# grip_strength_schematic.net
KiCad netlist of a schematic drawn in EAGLE
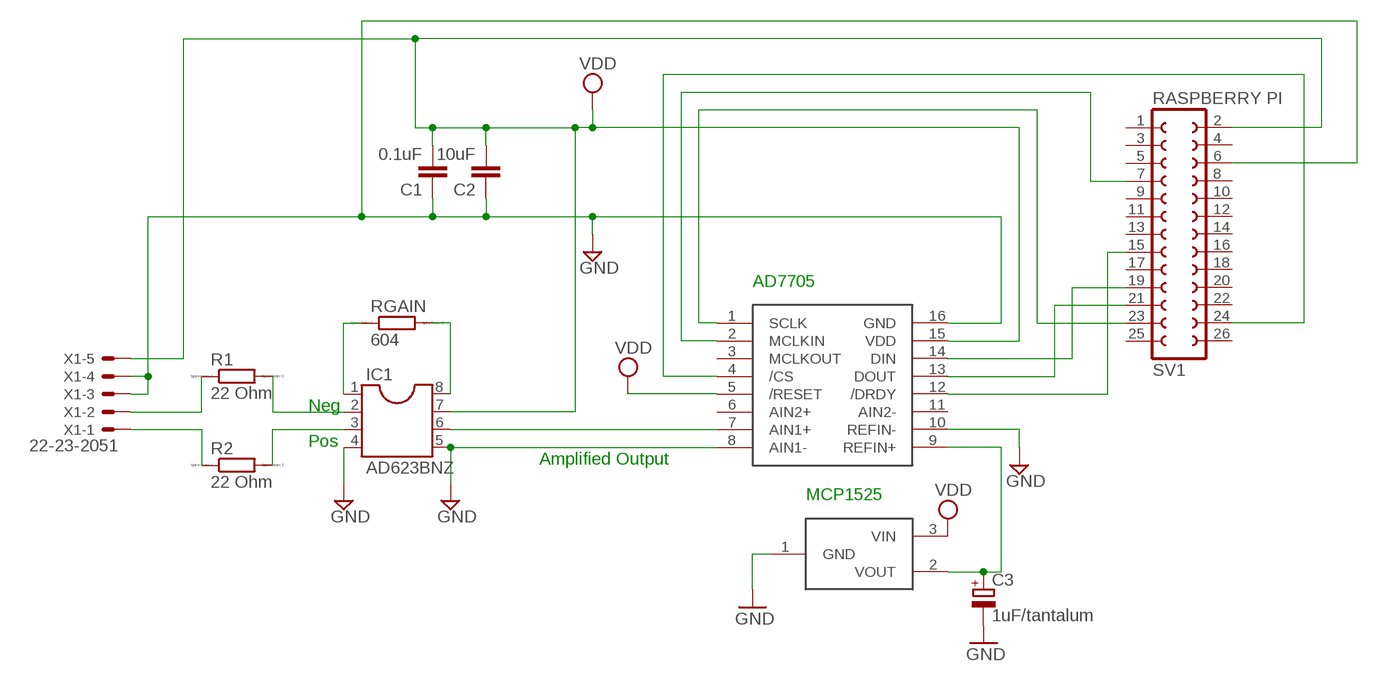
[diagram p0: schematic, sheet 1]

(export (version "E")
  (design (tool "Eeschema 10.0.6"))
  (components
    (comp (ref "C1")
      (value "0.1uF")
      (footprint "eagle-import:C5B2.5")
      (libsource (lib "eagle-import") (part "C5/2.5"))
    )
    (comp (ref "C2")
      (value "10uF")
      (footprint "eagle-import:C5B2.5")
      (libsource (lib "eagle-import") (part "C5/2.5"))
    )
    (comp (ref "C3")
      (value "1uF/tantalum")
      (footprint "eagle-import:TT2D7")
      (libsource (lib "eagle-import") (part "CPOL-EUTT2D7"))
    )
    (comp (ref "IC1")
      (value "AD623BNZ")
      (footprint "eagle-import:SOCKET-08")
      (libsource (lib "eagle-import") (part "DIL8S"))
    )
    (comp (ref "R1")
      (value "22 Ohm")
      (footprint "eagle-import:0207_10")
      (libsource (lib "eagle-import") (part "R0207/10"))
    )
    (comp (ref "R2")
      (value "22 Ohm")
      (footprint "eagle-import:0207_10")
      (libsource (lib "eagle-import") (part "R0207/10"))
    )
    (comp (ref "RGAIN")
      (value "604")
      (footprint "eagle-import:0207_10")
      (libsource (lib "eagle-import") (part "R0207/10"))
    )
    (comp (ref "SV1")
      (value "RASPBERRY PI")
      (footprint "eagle-import:FE13-2")
      (libsource (lib "eagle-import") (part "FE13-2"))
    )
    (comp (ref "U$1")
      (value "AD7705")
      (footprint "eagle-import:DIP16")
      (libsource (lib "eagle-import") (part "AD7705"))
    )
    (comp (ref "U$2")
      (value "MCP1525")
      (footprint "eagle-import:TO92")
      (libsource (lib "eagle-import") (part "MCP1525"))
    )
    (comp (ref "X1")
      (value "22-23-2051")
      (footprint "eagle-import:22-23-2051")
      (fields (field (name "MF") "MOLEX"))
      (libsource (lib "eagle-import") (part "22-23-2051"))
    )
  )
  (nets
    (net (code "1") (name "GND") (class "Default")
      (node (ref "C1") (pin "1") (pinfunction "1_1") (pintype "passive"))
      (node (ref "C2") (pin "1") (pinfunction "1_1") (pintype "passive"))
      (node (ref "C3") (pin "-") (pinfunction "-_-") (pintype "passive"))
      (node (ref "IC1") (pin "4") (pinfunction "4_4") (pintype "passive"))
      (node (ref "IC1") (pin "5") (pinfunction "5_5") (pintype "passive"))
      (node (ref "SV1") (pin "6") (pinfunction "6_6") (pintype "passive"))
      (node (ref "U$1") (pin "10") (pinfunction "REFIN-_10") (pintype "bidirectional"))
      (node (ref "U$1") (pin "16") (pinfunction "GND_16") (pintype "power_in"))
      (node (ref "U$1") (pin "8") (pinfunction "AIN1-_8") (pintype "bidirectional"))
      (node (ref "U$2") (pin "1") (pinfunction "GND_1") (pintype "power_in"))
      (node (ref "X1") (pin "3") (pinfunction "S_3") (pintype "passive"))
      (node (ref "X1") (pin "4") (pinfunction "S_4") (pintype "passive"))
    )
    (net (code "2") (name "Net-(IC1-Pad1)") (class "Default")
      (node (ref "IC1") (pin "1") (pinfunction "1_1") (pintype "passive"))
      (node (ref "RGAIN") (pin "1") (pinfunction "1_1") (pintype "passive"))
    )
    (net (code "3") (name "Net-(IC1-Pad2)") (class "Default")
      (node (ref "IC1") (pin "2") (pinfunction "2_2") (pintype "passive"))
      (node (ref "R1") (pin "2") (pinfunction "2_2") (pintype "passive"))
    )
    (net (code "4") (name "Net-(IC1-Pad3)") (class "Default")
      (node (ref "IC1") (pin "3") (pinfunction "3_3") (pintype "passive"))
      (node (ref "R2") (pin "2") (pinfunction "2_2") (pintype "passive"))
    )
    (net (code "5") (name "Net-(IC1-Pad8)") (class "Default")
      (node (ref "IC1") (pin "8") (pinfunction "8_8") (pintype "passive"))
      (node (ref "RGAIN") (pin "2") (pinfunction "2_2") (pintype "passive"))
    )
    (net (code "6") (name "Net-(U$1-AIN1+)") (class "Default")
      (node (ref "IC1") (pin "6") (pinfunction "6_6") (pintype "passive"))
      (node (ref "U$1") (pin "7") (pinfunction "AIN1+_7") (pintype "bidirectional"))
    )
    (net (code "7") (name "Net-(U$1-DIN)") (class "Default")
      (node (ref "SV1") (pin "19") (pinfunction "19_19") (pintype "passive"))
      (node (ref "U$1") (pin "14") (pinfunction "DIN_14") (pintype "bidirectional"))
    )
    (net (code "8") (name "Net-(U$1-DOUT)") (class "Default")
      (node (ref "SV1") (pin "21") (pinfunction "21_21") (pintype "passive"))
      (node (ref "U$1") (pin "13") (pinfunction "DOUT_13") (pintype "bidirectional"))
    )
    (net (code "9") (name "Net-(U$1-MCLKIN)") (class "Default")
      (node (ref "SV1") (pin "7") (pinfunction "7_7") (pintype "passive"))
      (node (ref "U$1") (pin "2") (pinfunction "MCLKIN_2") (pintype "bidirectional"))
    )
    (net (code "10") (name "Net-(U$1-REFIN+)") (class "Default")
      (node (ref "C3") (pin "+") (pinfunction "+_+") (pintype "passive"))
      (node (ref "U$1") (pin "9") (pinfunction "REFIN+_9") (pintype "bidirectional"))
      (node (ref "U$2") (pin "2") (pinfunction "VOUT_2") (pintype "power_in"))
    )
    (net (code "11") (name "Net-(U$1-SCLK)") (class "Default")
      (node (ref "SV1") (pin "23") (pinfunction "23_23") (pintype "passive"))
      (node (ref "U$1") (pin "1") (pinfunction "SCLK_1") (pintype "bidirectional"))
    )
    (net (code "12") (name "Net-(U$1-{slash}CS)") (class "Default")
      (node (ref "SV1") (pin "24") (pinfunction "24_24") (pintype "passive"))
      (node (ref "U$1") (pin "4") (pinfunction "/CS_4") (pintype "bidirectional"))
    )
    (net (code "13") (name "Net-(U$1-{slash}DRDY)") (class "Default")
      (node (ref "SV1") (pin "15") (pinfunction "15_15") (pintype "passive"))
      (node (ref "U$1") (pin "12") (pinfunction "/DRDY_12") (pintype "bidirectional"))
    )
    (net (code "14") (name "Net-(X1A-S)") (class "Default")
      (node (ref "R2") (pin "1") (pinfunction "1_1") (pintype "passive"))
      (node (ref "X1") (pin "1") (pinfunction "S_1") (pintype "passive"))
    )
    (net (code "15") (name "Net-(X1B-S)") (class "Default")
      (node (ref "R1") (pin "1") (pinfunction "1_1") (pintype "passive"))
      (node (ref "X1") (pin "2") (pinfunction "S_2") (pintype "passive"))
    )
    (net (code "16") (name "VDD") (class "Default")
      (node (ref "C1") (pin "2") (pinfunction "2_2") (pintype "passive"))
      (node (ref "C2") (pin "2") (pinfunction "2_2") (pintype "passive"))
      (node (ref "IC1") (pin "7") (pinfunction "7_7") (pintype "passive"))
      (node (ref "SV1") (pin "2") (pinfunction "2_2") (pintype "passive"))
      (node (ref "U$1") (pin "15") (pinfunction "VDD_15") (pintype "power_in"))
      (node (ref "U$1") (pin "5") (pinfunction "/RESET_5") (pintype "bidirectional"))
      (node (ref "U$2") (pin "3") (pinfunction "VIN_3") (pintype "power_in"))
      (node (ref "X1") (pin "5") (pinfunction "S_5") (pintype "passive"))
    )
    (net (code "17") (name "unconnected-(SV1-Pad1)") (class "Default")
      (node (ref "SV1") (pin "1") (pinfunction "1_1") (pintype "passive"))
    )
    (net (code "18") (name "unconnected-(SV1-Pad3)") (class "Default")
      (node (ref "SV1") (pin "3") (pinfunction "3_3") (pintype "passive"))
    )
    (net (code "19") (name "unconnected-(SV1-Pad4)") (class "Default")
      (node (ref "SV1") (pin "4") (pinfunction "4_4") (pintype "passive"))
    )
    (net (code "20") (name "unconnected-(SV1-Pad5)") (class "Default")
      (node (ref "SV1") (pin "5") (pinfunction "5_5") (pintype "passive"))
    )
    (net (code "21") (name "unconnected-(SV1-Pad8)") (class "Default")
      (node (ref "SV1") (pin "8") (pinfunction "8_8") (pintype "passive"))
    )
    (net (code "22") (name "unconnected-(SV1-Pad9)") (class "Default")
      (node (ref "SV1") (pin "9") (pinfunction "9_9") (pintype "passive"))
    )
    (net (code "23") (name "unconnected-(SV1-Pad10)") (class "Default")
      (node (ref "SV1") (pin "10") (pinfunction "10_10") (pintype "passive"))
    )
    (net (code "24") (name "unconnected-(SV1-Pad11)") (class "Default")
      (node (ref "SV1") (pin "11") (pinfunction "11_11") (pintype "passive"))
    )
    (net (code "25") (name "unconnected-(SV1-Pad12)") (class "Default")
      (node (ref "SV1") (pin "12") (pinfunction "12_12") (pintype "passive"))
    )
    (net (code "26") (name "unconnected-(SV1-Pad13)") (class "Default")
      (node (ref "SV1") (pin "13") (pinfunction "13_13") (pintype "passive"))
    )
    (net (code "27") (name "unconnected-(SV1-Pad14)") (class "Default")
      (node (ref "SV1") (pin "14") (pinfunction "14_14") (pintype "passive"))
    )
    (net (code "28") (name "unconnected-(SV1-Pad16)") (class "Default")
      (node (ref "SV1") (pin "16") (pinfunction "16_16") (pintype "passive"))
    )
    (net (code "29") (name "unconnected-(SV1-Pad17)") (class "Default")
      (node (ref "SV1") (pin "17") (pinfunction "17_17") (pintype "passive"))
    )
    (net (code "30") (name "unconnected-(SV1-Pad18)") (class "Default")
      (node (ref "SV1") (pin "18") (pinfunction "18_18") (pintype "passive"))
    )
    (net (code "31") (name "unconnected-(SV1-Pad20)") (class "Default")
      (node (ref "SV1") (pin "20") (pinfunction "20_20") (pintype "passive"))
    )
    (net (code "32") (name "unconnected-(SV1-Pad22)") (class "Default")
      (node (ref "SV1") (pin "22") (pinfunction "22_22") (pintype "passive"))
    )
    (net (code "33") (name "unconnected-(SV1-Pad25)") (class "Default")
      (node (ref "SV1") (pin "25") (pinfunction "25_25") (pintype "passive"))
    )
    (net (code "34") (name "unconnected-(SV1-Pad26)") (class "Default")
      (node (ref "SV1") (pin "26") (pinfunction "26_26") (pintype "passive"))
    )
    (net (code "35") (name "unconnected-(U$1-AIN2+-Pad6)") (class "Default")
      (node (ref "U$1") (pin "6") (pinfunction "AIN2+_6") (pintype "bidirectional"))
    )
    (net (code "36") (name "unconnected-(U$1-AIN2--Pad11)") (class "Default")
      (node (ref "U$1") (pin "11") (pinfunction "AIN2-_11") (pintype "bidirectional"))
    )
    (net (code "37") (name "unconnected-(U$1-MCLKOUT-Pad3)") (class "Default")
      (node (ref "U$1") (pin "3") (pinfunction "MCLKOUT_3") (pintype "bidirectional"))
    )
  )
)
